# UpTo11_MotherBoard.net
KiCad netlist of a schematic drawn in EAGLE
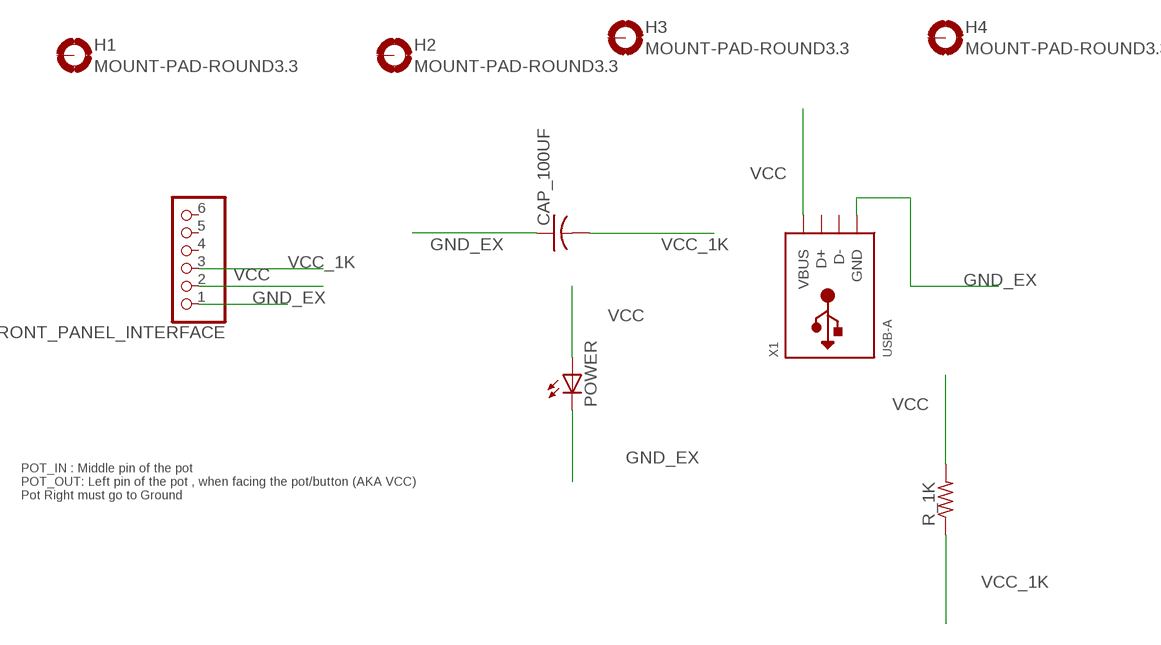
[diagram p0: schematic, sheet 1]

(export (version "E")
  (design (tool "Eeschema 10.0.6"))
  (components
    (comp (ref "CAP_100UF")
      (value "C-US025-030X050")
      (footprint "eagle-import:C025-030X050")
      (libsource (lib "eagle-import") (part "C-US025-030X050"))
    )
    (comp (ref "FRONT_PANEL_INTERFACE")
      (value "PINHD-1X6")
      (footprint "eagle-import:1X06")
      (libsource (lib "eagle-import") (part "PINHD-1X6"))
    )
    (comp (ref "H1")
      (value "MOUNT-PAD-ROUND3.3")
      (footprint "eagle-import:3,3-PAD")
      (libsource (lib "eagle-import") (part "MOUNT-PAD-ROUND3.3"))
    )
    (comp (ref "H2")
      (value "MOUNT-PAD-ROUND3.3")
      (footprint "eagle-import:3,3-PAD")
      (libsource (lib "eagle-import") (part "MOUNT-PAD-ROUND3.3"))
    )
    (comp (ref "H3")
      (value "MOUNT-PAD-ROUND3.3")
      (footprint "eagle-import:3,3-PAD")
      (libsource (lib "eagle-import") (part "MOUNT-PAD-ROUND3.3"))
    )
    (comp (ref "H4")
      (value "MOUNT-PAD-ROUND3.3")
      (footprint "eagle-import:3,3-PAD")
      (libsource (lib "eagle-import") (part "MOUNT-PAD-ROUND3.3"))
    )
    (comp (ref "POWER")
      (value "LEDSMT1206")
      (footprint "eagle-import:1206")
      (libsource (lib "eagle-import") (part "LEDSMT1206"))
    )
    (comp (ref "R_1K")
      (value "R-US_R1206")
      (footprint "eagle-import:R1206")
      (libsource (lib "eagle-import") (part "R-US_R1206"))
    )
    (comp (ref "X1")
      (value "USB-A")
      (footprint "eagle-import:MOLEX_480371000")
      (libsource (lib "eagle-import") (part "USB-A"))
    )
  )
  (nets
    (net (code "1") (name "/GND_EX") (class "Default")
      (node (ref "CAP_100UF") (pin "1") (pinfunction "1_1") (pintype "passive"))
      (node (ref "FRONT_PANEL_INTERFACE") (pin "1") (pinfunction "1_1") (pintype "passive"))
      (node (ref "POWER") (pin "C") (pinfunction "C_C") (pintype "passive"))
      (node (ref "X1") (pin "4") (pinfunction "GND_4") (pintype "power_in"))
    )
    (net (code "2") (name "/VCC") (class "Default")
      (node (ref "FRONT_PANEL_INTERFACE") (pin "2") (pinfunction "2_2") (pintype "passive"))
      (node (ref "POWER") (pin "A") (pinfunction "A_A") (pintype "passive"))
      (node (ref "R_1K") (pin "2") (pinfunction "2_2") (pintype "passive"))
      (node (ref "X1") (pin "1") (pinfunction "VBUS_1") (pintype "power_in"))
    )
    (net (code "3") (name "/VCC_1K") (class "Default")
      (node (ref "CAP_100UF") (pin "2") (pinfunction "2_2") (pintype "passive"))
      (node (ref "FRONT_PANEL_INTERFACE") (pin "3") (pinfunction "3_3") (pintype "passive"))
      (node (ref "R_1K") (pin "1") (pinfunction "1_1") (pintype "passive"))
    )
    (net (code "4") (name "unconnected-(FRONT_PANEL_INTERFACE-Pad4)") (class "Default")
      (node (ref "FRONT_PANEL_INTERFACE") (pin "4") (pinfunction "4_4") (pintype "passive"))
    )
    (net (code "5") (name "unconnected-(FRONT_PANEL_INTERFACE-Pad5)") (class "Default")
      (node (ref "FRONT_PANEL_INTERFACE") (pin "5") (pinfunction "5_5") (pintype "passive"))
    )
    (net (code "6") (name "unconnected-(FRONT_PANEL_INTERFACE-Pad6)") (class "Default")
      (node (ref "FRONT_PANEL_INTERFACE") (pin "6") (pinfunction "6_6") (pintype "passive"))
    )
    (net (code "7") (name "unconnected-(H1-MOUNT-PadB3,3)") (class "Default")
      (node (ref "H1") (pin "B3,3") (pinfunction "MOUNT_B3,3") (pintype "passive"))
    )
    (net (code "8") (name "unconnected-(H2-MOUNT-PadB3,3)") (class "Default")
      (node (ref "H2") (pin "B3,3") (pinfunction "MOUNT_B3,3") (pintype "passive"))
    )
    (net (code "9") (name "unconnected-(H3-MOUNT-PadB3,3)") (class "Default")
      (node (ref "H3") (pin "B3,3") (pinfunction "MOUNT_B3,3") (pintype "passive"))
    )
    (net (code "10") (name "unconnected-(H4-MOUNT-PadB3,3)") (class "Default")
      (node (ref "H4") (pin "B3,3") (pinfunction "MOUNT_B3,3") (pintype "passive"))
    )
    (net (code "11") (name "unconnected-(X1-D+-Pad3)") (class "Default")
      (node (ref "X1") (pin "3") (pinfunction "D+_3") (pintype "bidirectional"))
    )
    (net (code "12") (name "unconnected-(X1-D--Pad2)") (class "Default")
      (node (ref "X1") (pin "2") (pinfunction "D-_2") (pintype "bidirectional"))
    )
  )
)
